# 51-039.net
KiCad netlist of a schematic drawn in Altium Designer
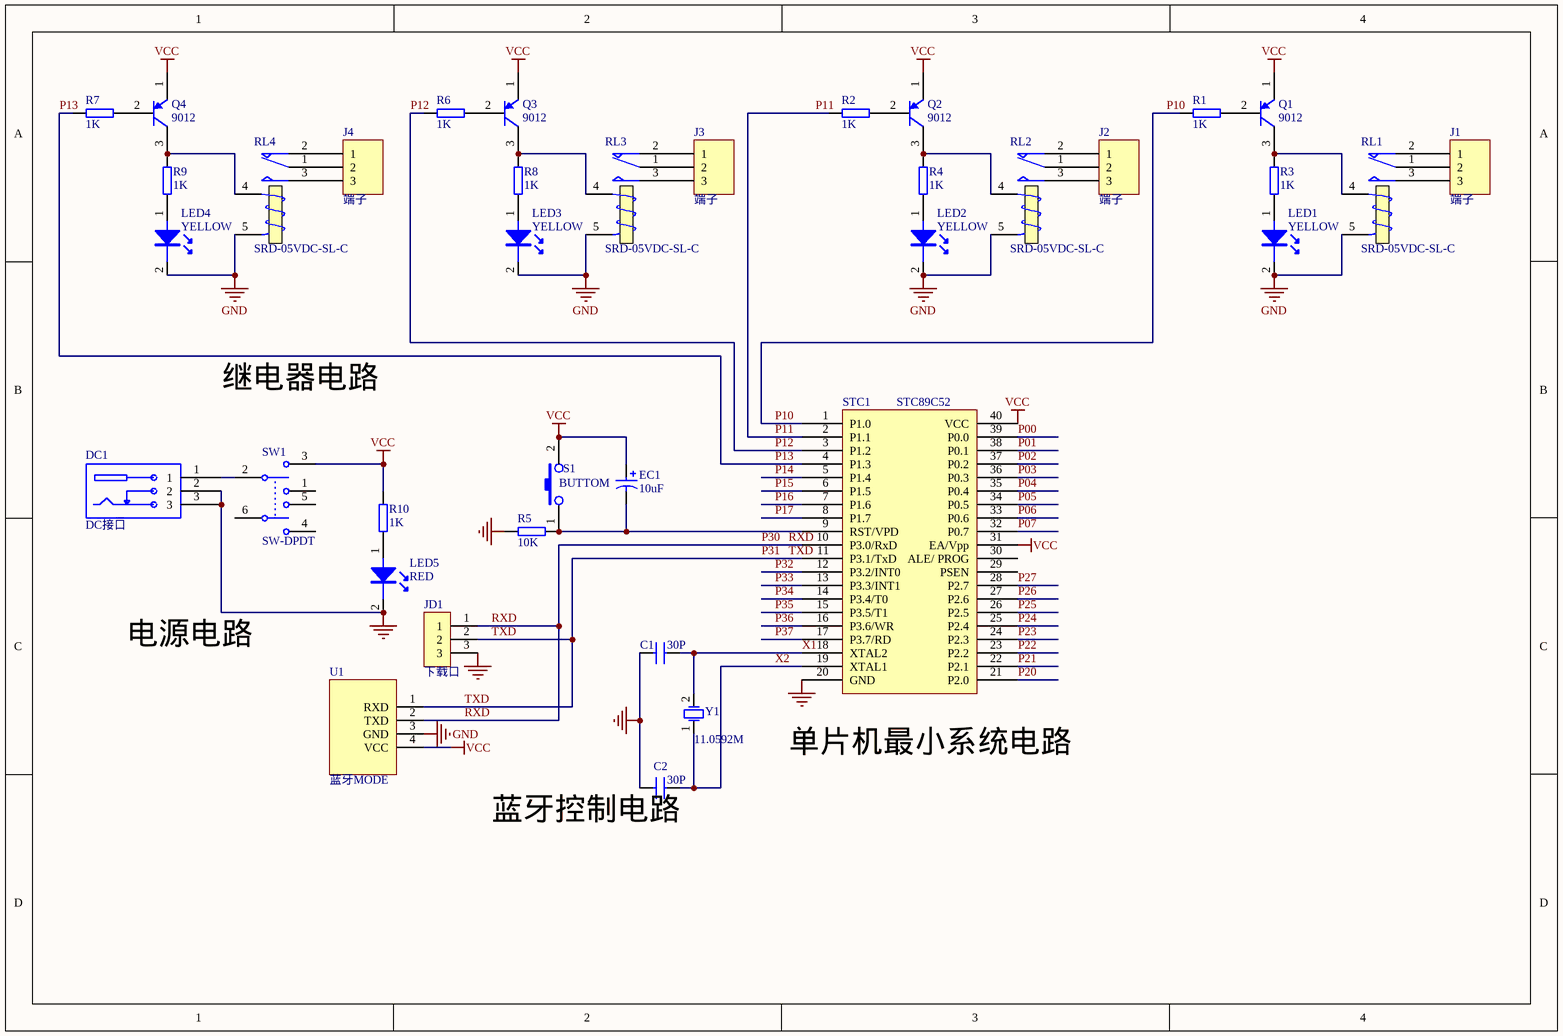
[diagram p0: 51-039原理图（源文件格式）.SCHDOC]

(export (version "E")
  (design (tool "Eeschema 10.0.6"))
  (components
    (comp (ref "C1")
      (value "30P")
      (footprint "RAD-0.1")
      (description "无极性电容")
      (libsource (lib "参考") (part "CAP"))
    )
    (comp (ref "C2")
      (value "30P")
      (footprint "RAD-0.1")
      (description "无极性电容")
      (libsource (lib "参考") (part "CAP"))
    )
    (comp (ref "DC1")
      (value "DC接口")
      (footprint "DC-JACK-002")
      (description "DC接口（分大小）")
      (libsource (lib "参考") (part "DC接口"))
    )
    (comp (ref "EC1")
      (value "10uF")
      (footprint "RB.1/.2")
      (description "极性电容")
      (libsource (lib "参考") (part "CAP_EC"))
    )
    (comp (ref "J1")
      (value "端子")
      (footprint "5.08三芯接线端子")
      (description "接线端子3芯")
      (fields (field (name "PUBLISHER") "Altium Limited"))
      (libsource (lib "参考") (part "CON3"))
    )
    (comp (ref "J2")
      (value "端子")
      (footprint "5.08三芯接线端子")
      (description "接线端子3芯")
      (fields (field (name "PUBLISHER") "Altium Limited"))
      (libsource (lib "参考") (part "CON3"))
    )
    (comp (ref "J3")
      (value "端子")
      (footprint "5.08三芯接线端子")
      (description "接线端子3芯")
      (fields (field (name "PUBLISHER") "Altium Limited"))
      (libsource (lib "参考") (part "CON3"))
    )
    (comp (ref "J4")
      (value "端子")
      (footprint "5.08三芯接线端子")
      (description "接线端子3芯")
      (fields (field (name "PUBLISHER") "Altium Limited"))
      (libsource (lib "参考") (part "CON3"))
    )
    (comp (ref "JD1")
      (value "下载口")
      (footprint "下载串口")
      (description "下载口2.54排针")
      (libsource (lib "参考") (part "下载口"))
    )
    (comp (ref "LED1")
      (value "YELLOW")
      (footprint "LED_D3MM12")
      (description "LED灯")
      (libsource (lib "参考") (part "LED"))
    )
    (comp (ref "LED2")
      (value "YELLOW")
      (footprint "LED_D3MM12")
      (description "LED灯")
      (libsource (lib "参考") (part "LED"))
    )
    (comp (ref "LED3")
      (value "YELLOW")
      (footprint "LED_D3MM12")
      (description "LED灯")
      (libsource (lib "参考") (part "LED"))
    )
    (comp (ref "LED4")
      (value "YELLOW")
      (footprint "LED_D3MM12")
      (description "LED灯")
      (libsource (lib "参考") (part "LED"))
    )
    (comp (ref "LED5")
      (value "RED")
      (footprint "LED_D3MM12")
      (description "LED灯")
      (libsource (lib "参考") (part "LED"))
    )
    (comp (ref "Q1")
      (value "9012")
      (footprint "TO-92")
      (description "直插三极管")
      (libsource (lib "参考") (part "9012"))
    )
    (comp (ref "Q2")
      (value "9012")
      (footprint "TO-92")
      (description "直插三极管")
      (libsource (lib "参考") (part "9012"))
    )
    (comp (ref "Q3")
      (value "9012")
      (footprint "TO-92")
      (description "直插三极管")
      (libsource (lib "参考") (part "9012"))
    )
    (comp (ref "Q4")
      (value "9012")
      (footprint "TO-92")
      (description "直插三极管")
      (libsource (lib "参考") (part "9012"))
    )
    (comp (ref "R1")
      (value "1K")
      (footprint "AXIAL0.3")
      (description "电阻")
      (libsource (lib "参考") (part "RES"))
    )
    (comp (ref "R2")
      (value "1K")
      (footprint "AXIAL0.3")
      (description "电阻")
      (libsource (lib "参考") (part "RES"))
    )
    (comp (ref "R3")
      (value "1K")
      (footprint "AXIAL0.3")
      (description "电阻")
      (libsource (lib "参考") (part "RES"))
    )
    (comp (ref "R4")
      (value "1K")
      (footprint "AXIAL0.3")
      (description "电阻")
      (libsource (lib "参考") (part "RES"))
    )
    (comp (ref "R5")
      (value "10K")
      (footprint "AXIAL0.3")
      (description "电阻")
      (libsource (lib "参考") (part "RES"))
    )
    (comp (ref "R6")
      (value "1K")
      (footprint "AXIAL0.3")
      (description "电阻")
      (libsource (lib "参考") (part "RES"))
    )
    (comp (ref "R7")
      (value "1K")
      (footprint "AXIAL0.3")
      (description "电阻")
      (libsource (lib "参考") (part "RES"))
    )
    (comp (ref "R8")
      (value "1K")
      (footprint "AXIAL0.3")
      (description "电阻")
      (libsource (lib "参考") (part "RES"))
    )
    (comp (ref "R9")
      (value "1K")
      (footprint "AXIAL0.3")
      (description "电阻")
      (libsource (lib "参考") (part "RES"))
    )
    (comp (ref "R10")
      (value "1K")
      (footprint "AXIAL0.3")
      (description "电阻")
      (libsource (lib "参考") (part "RES"))
    )
    (comp (ref "RL1")
      (value "SRD-05VDC-SL-C")
      (footprint "RELAY_5V51BOARD")
      (description "继电器")
      (fields (field (name "PUBLISHER") "Altium Limited"))
      (libsource (lib "参考") (part "RELAY"))
    )
    (comp (ref "RL2")
      (value "SRD-05VDC-SL-C")
      (footprint "RELAY_5V51BOARD")
      (description "继电器")
      (fields (field (name "PUBLISHER") "Altium Limited"))
      (libsource (lib "参考") (part "RELAY"))
    )
    (comp (ref "RL3")
      (value "SRD-05VDC-SL-C")
      (footprint "RELAY_5V51BOARD")
      (description "继电器")
      (fields (field (name "PUBLISHER") "Altium Limited"))
      (libsource (lib "参考") (part "RELAY"))
    )
    (comp (ref "RL4")
      (value "SRD-05VDC-SL-C")
      (footprint "RELAY_5V51BOARD")
      (description "继电器")
      (fields (field (name "PUBLISHER") "Altium Limited"))
      (libsource (lib "参考") (part "RELAY"))
    )
    (comp (ref "S1")
      (value "BUTTOM")
      (footprint "BUTTOM_6x6DIP")
      (description "按键")
      (libsource (lib "参考") (part "BUTTOM"))
    )
    (comp (ref "STC1")
      (value "STC89C52")
      (footprint "STC89")
      (description "51单片机")
      (libsource (lib "参考") (part "STC51"))
    )
    (comp (ref "SW1")
      (value "SW-DPDT")
      (footprint "SW")
      (description "电源开关")
      (fields (field (name "PUBLISHER") "Altium Limited"))
      (libsource (lib "参考") (part "SW-DPDT"))
    )
    (comp (ref "U1")
      (value "蓝牙MODE")
      (footprint "蓝牙MODE竖放")
      (description "蓝牙模块")
      (libsource (lib "参考") (part "蓝牙MODE"))
    )
    (comp (ref "Y1")
      (value "11.0592M")
      (footprint "X_HC-49")
      (description "晶振")
      (libsource (lib "参考") (part "XTAL DIP"))
    )
  )
  (nets
    (net (code "1") (name "/P00") (class "Default")
      (node (ref "STC1") (pin "39") (pinfunction "P0.0_39") (pintype "passive"))
    )
    (net (code "2") (name "/P01") (class "Default")
      (node (ref "STC1") (pin "38") (pinfunction "P0.1_38") (pintype "passive"))
    )
    (net (code "3") (name "/P02") (class "Default")
      (node (ref "STC1") (pin "37") (pinfunction "P0.2_37") (pintype "passive"))
    )
    (net (code "4") (name "/P03") (class "Default")
      (node (ref "STC1") (pin "36") (pinfunction "P0.3_36") (pintype "passive"))
    )
    (net (code "5") (name "/P04") (class "Default")
      (node (ref "STC1") (pin "35") (pinfunction "P0.4_35") (pintype "passive"))
    )
    (net (code "6") (name "/P05") (class "Default")
      (node (ref "STC1") (pin "34") (pinfunction "P0.5_34") (pintype "passive"))
    )
    (net (code "7") (name "/P06") (class "Default")
      (node (ref "STC1") (pin "33") (pinfunction "P0.6_33") (pintype "passive"))
    )
    (net (code "8") (name "/P07") (class "Default")
      (node (ref "STC1") (pin "32") (pinfunction "P0.7_32") (pintype "passive"))
    )
    (net (code "9") (name "/P10") (class "Default")
      (node (ref "R1") (pin "2") (pinfunction "2_2") (pintype "passive"))
      (node (ref "STC1") (pin "1") (pinfunction "P1.0_1") (pintype "passive"))
    )
    (net (code "10") (name "/P11") (class "Default")
      (node (ref "R2") (pin "2") (pinfunction "2_2") (pintype "passive"))
      (node (ref "STC1") (pin "2") (pinfunction "P1.1_2") (pintype "passive"))
    )
    (net (code "11") (name "/P12") (class "Default")
      (node (ref "R6") (pin "2") (pinfunction "2_2") (pintype "passive"))
      (node (ref "STC1") (pin "3") (pinfunction "P1.2_3") (pintype "passive"))
    )
    (net (code "12") (name "/P13") (class "Default")
      (node (ref "R7") (pin "2") (pinfunction "2_2") (pintype "passive"))
      (node (ref "STC1") (pin "4") (pinfunction "P1.3_4") (pintype "passive"))
    )
    (net (code "13") (name "/P14") (class "Default")
      (node (ref "STC1") (pin "5") (pinfunction "P1.4_5") (pintype "passive"))
    )
    (net (code "14") (name "/P15") (class "Default")
      (node (ref "STC1") (pin "6") (pinfunction "P1.5_6") (pintype "passive"))
    )
    (net (code "15") (name "/P16") (class "Default")
      (node (ref "STC1") (pin "7") (pinfunction "P1.6_7") (pintype "passive"))
    )
    (net (code "16") (name "/P17") (class "Default")
      (node (ref "STC1") (pin "8") (pinfunction "P1.7_8") (pintype "passive"))
    )
    (net (code "17") (name "/P20") (class "Default")
      (node (ref "STC1") (pin "21") (pinfunction "P2.0_21") (pintype "passive"))
    )
    (net (code "18") (name "/P21") (class "Default")
      (node (ref "STC1") (pin "22") (pinfunction "P2.1_22") (pintype "passive"))
    )
    (net (code "19") (name "/P22") (class "Default")
      (node (ref "STC1") (pin "23") (pinfunction "P2.2_23") (pintype "passive"))
    )
    (net (code "20") (name "/P23") (class "Default")
      (node (ref "STC1") (pin "24") (pinfunction "P2.3_24") (pintype "passive"))
    )
    (net (code "21") (name "/P24") (class "Default")
      (node (ref "STC1") (pin "25") (pinfunction "P2.4_25") (pintype "passive"))
    )
    (net (code "22") (name "/P25") (class "Default")
      (node (ref "STC1") (pin "26") (pinfunction "P2.5_26") (pintype "passive"))
    )
    (net (code "23") (name "/P26") (class "Default")
      (node (ref "STC1") (pin "27") (pinfunction "P2.6_27") (pintype "passive"))
    )
    (net (code "24") (name "/P27") (class "Default")
      (node (ref "STC1") (pin "28") (pinfunction "P2.7_28") (pintype "passive"))
    )
    (net (code "25") (name "/P30") (class "Default")
      (node (ref "JD1") (pin "1") (pinfunction "1_1") (pintype "passive"))
      (node (ref "STC1") (pin "10") (pinfunction "P3.0/RxD_10") (pintype "passive"))
      (node (ref "U1") (pin "2") (pinfunction "TXD_2") (pintype "passive"))
    )
    (net (code "26") (name "/P31") (class "Default")
      (node (ref "JD1") (pin "2") (pinfunction "2_2") (pintype "passive"))
      (node (ref "STC1") (pin "11") (pinfunction "P3.1/TxD_11") (pintype "passive"))
      (node (ref "U1") (pin "1") (pinfunction "RXD_1") (pintype "passive"))
    )
    (net (code "27") (name "/P32") (class "Default")
      (node (ref "STC1") (pin "12") (pinfunction "P3.2/INT0_12") (pintype "passive"))
    )
    (net (code "28") (name "/P33") (class "Default")
      (node (ref "STC1") (pin "13") (pinfunction "P3.3/INT1_13") (pintype "passive"))
    )
    (net (code "29") (name "/P34") (class "Default")
      (node (ref "STC1") (pin "14") (pinfunction "P3.4/T0_14") (pintype "passive"))
    )
    (net (code "30") (name "/P35") (class "Default")
      (node (ref "STC1") (pin "15") (pinfunction "P3.5/T1_15") (pintype "passive"))
    )
    (net (code "31") (name "/P36") (class "Default")
      (node (ref "STC1") (pin "16") (pinfunction "P3.6/WR_16") (pintype "passive"))
    )
    (net (code "32") (name "/P37") (class "Default")
      (node (ref "STC1") (pin "17") (pinfunction "P3.7/RD_17") (pintype "passive"))
    )
    (net (code "33") (name "/X1") (class "Default")
      (node (ref "C1") (pin "2") (pinfunction "2_2") (pintype "passive"))
      (node (ref "STC1") (pin "18") (pinfunction "XTAL2_18") (pintype "passive"))
      (node (ref "Y1") (pin "2") (pinfunction "OSC2_2") (pintype "passive"))
    )
    (net (code "34") (name "/X2") (class "Default")
      (node (ref "C2") (pin "2") (pinfunction "2_2") (pintype "passive"))
      (node (ref "STC1") (pin "19") (pinfunction "XTAL1_19") (pintype "passive"))
      (node (ref "Y1") (pin "1") (pinfunction "OSC1_1") (pintype "passive"))
    )
    (net (code "35") (name "GND") (class "Default")
      (node (ref "C1") (pin "1") (pinfunction "1_1") (pintype "passive"))
      (node (ref "C2") (pin "1") (pinfunction "1_1") (pintype "passive"))
      (node (ref "DC1") (pin "2") (pinfunction "2_2") (pintype "passive"))
      (node (ref "DC1") (pin "3") (pinfunction "3_3") (pintype "passive"))
      (node (ref "JD1") (pin "3") (pinfunction "3_3") (pintype "passive"))
      (node (ref "LED1") (pin "2") (pinfunction "2_2") (pintype "passive"))
      (node (ref "LED2") (pin "2") (pinfunction "2_2") (pintype "passive"))
      (node (ref "LED3") (pin "2") (pinfunction "2_2") (pintype "passive"))
      (node (ref "LED4") (pin "2") (pinfunction "2_2") (pintype "passive"))
      (node (ref "LED5") (pin "2") (pinfunction "2_2") (pintype "passive"))
      (node (ref "R5") (pin "1") (pinfunction "1_1") (pintype "passive"))
      (node (ref "RL1") (pin "5") (pinfunction "T2_5") (pintype "passive"))
      (node (ref "RL2") (pin "5") (pinfunction "T2_5") (pintype "passive"))
      (node (ref "RL3") (pin "5") (pinfunction "T2_5") (pintype "passive"))
      (node (ref "RL4") (pin "5") (pinfunction "T2_5") (pintype "passive"))
      (node (ref "STC1") (pin "20") (pinfunction "GND_20") (pintype "passive"))
      (node (ref "U1") (pin "3") (pinfunction "GND_3") (pintype "passive"))
    )
    (net (code "36") (name "Net-(DC1-Pad1)") (class "Default")
      (node (ref "DC1") (pin "1") (pinfunction "1_1") (pintype "passive"))
      (node (ref "SW1") (pin "2") (pinfunction "2_2") (pintype "passive"))
    )
    (net (code "37") (name "Net-(LED1-Pad1)") (class "Default")
      (node (ref "LED1") (pin "1") (pinfunction "1_1") (pintype "passive"))
      (node (ref "R3") (pin "2") (pinfunction "2_2") (pintype "passive"))
    )
    (net (code "38") (name "Net-(LED2-Pad1)") (class "Default")
      (node (ref "LED2") (pin "1") (pinfunction "1_1") (pintype "passive"))
      (node (ref "R4") (pin "2") (pinfunction "2_2") (pintype "passive"))
    )
    (net (code "39") (name "Net-(LED3-Pad1)") (class "Default")
      (node (ref "LED3") (pin "1") (pinfunction "1_1") (pintype "passive"))
      (node (ref "R8") (pin "2") (pinfunction "2_2") (pintype "passive"))
    )
    (net (code "40") (name "Net-(LED4-Pad1)") (class "Default")
      (node (ref "LED4") (pin "1") (pinfunction "1_1") (pintype "passive"))
      (node (ref "R9") (pin "2") (pinfunction "2_2") (pintype "passive"))
    )
    (net (code "41") (name "Net-(LED5-Pad1)") (class "Default")
      (node (ref "LED5") (pin "1") (pinfunction "1_1") (pintype "passive"))
      (node (ref "R10") (pin "1") (pinfunction "1_1") (pintype "passive"))
    )
    (net (code "42") (name "Net-(Q1-b)") (class "Default")
      (node (ref "Q1") (pin "2") (pinfunction "b_2") (pintype "passive"))
      (node (ref "R1") (pin "1") (pinfunction "1_1") (pintype "passive"))
    )
    (net (code "43") (name "Net-(Q1-c)") (class "Default")
      (node (ref "Q1") (pin "3") (pinfunction "c_3") (pintype "passive"))
      (node (ref "R3") (pin "1") (pinfunction "1_1") (pintype "passive"))
      (node (ref "RL1") (pin "4") (pinfunction "T1_4") (pintype "passive"))
    )
    (net (code "44") (name "Net-(Q2-b)") (class "Default")
      (node (ref "Q2") (pin "2") (pinfunction "b_2") (pintype "passive"))
      (node (ref "R2") (pin "1") (pinfunction "1_1") (pintype "passive"))
    )
    (net (code "45") (name "Net-(Q2-c)") (class "Default")
      (node (ref "Q2") (pin "3") (pinfunction "c_3") (pintype "passive"))
      (node (ref "R4") (pin "1") (pinfunction "1_1") (pintype "passive"))
      (node (ref "RL2") (pin "4") (pinfunction "T1_4") (pintype "passive"))
    )
    (net (code "46") (name "Net-(Q3-b)") (class "Default")
      (node (ref "Q3") (pin "2") (pinfunction "b_2") (pintype "passive"))
      (node (ref "R6") (pin "1") (pinfunction "1_1") (pintype "passive"))
    )
    (net (code "47") (name "Net-(Q3-c)") (class "Default")
      (node (ref "Q3") (pin "3") (pinfunction "c_3") (pintype "passive"))
      (node (ref "R8") (pin "1") (pinfunction "1_1") (pintype "passive"))
      (node (ref "RL3") (pin "4") (pinfunction "T1_4") (pintype "passive"))
    )
    (net (code "48") (name "Net-(Q4-b)") (class "Default")
      (node (ref "Q4") (pin "2") (pinfunction "b_2") (pintype "passive"))
      (node (ref "R7") (pin "1") (pinfunction "1_1") (pintype "passive"))
    )
    (net (code "49") (name "Net-(Q4-c)") (class "Default")
      (node (ref "Q4") (pin "3") (pinfunction "c_3") (pintype "passive"))
      (node (ref "R9") (pin "1") (pinfunction "1_1") (pintype "passive"))
      (node (ref "RL4") (pin "4") (pinfunction "T1_4") (pintype "passive"))
    )
    (net (code "50") (name "Net-(RL1-COM)") (class "Default")
      (node (ref "J1") (pin "2") (pinfunction "2_2") (pintype "passive"))
      (node (ref "RL1") (pin "1") (pinfunction "COM_1") (pintype "passive"))
    )
    (net (code "51") (name "Net-(RL1-NC)") (class "Default")
      (node (ref "J1") (pin "1") (pinfunction "1_1") (pintype "passive"))
      (node (ref "RL1") (pin "2") (pinfunction "NC_2") (pintype "passive"))
    )
    (net (code "52") (name "Net-(RL1-NO)") (class "Default")
      (node (ref "J1") (pin "3") (pinfunction "3_3") (pintype "passive"))
      (node (ref "RL1") (pin "3") (pinfunction "NO_3") (pintype "passive"))
    )
    (net (code "53") (name "Net-(RL2-COM)") (class "Default")
      (node (ref "J2") (pin "2") (pinfunction "2_2") (pintype "passive"))
      (node (ref "RL2") (pin "1") (pinfunction "COM_1") (pintype "passive"))
    )
    (net (code "54") (name "Net-(RL2-NC)") (class "Default")
      (node (ref "J2") (pin "1") (pinfunction "1_1") (pintype "passive"))
      (node (ref "RL2") (pin "2") (pinfunction "NC_2") (pintype "passive"))
    )
    (net (code "55") (name "Net-(RL2-NO)") (class "Default")
      (node (ref "J2") (pin "3") (pinfunction "3_3") (pintype "passive"))
      (node (ref "RL2") (pin "3") (pinfunction "NO_3") (pintype "passive"))
    )
    (net (code "56") (name "Net-(RL3-COM)") (class "Default")
      (node (ref "J3") (pin "2") (pinfunction "2_2") (pintype "passive"))
      (node (ref "RL3") (pin "1") (pinfunction "COM_1") (pintype "passive"))
    )
    (net (code "57") (name "Net-(RL3-NC)") (class "Default")
      (node (ref "J3") (pin "1") (pinfunction "1_1") (pintype "passive"))
      (node (ref "RL3") (pin "2") (pinfunction "NC_2") (pintype "passive"))
    )
    (net (code "58") (name "Net-(RL3-NO)") (class "Default")
      (node (ref "J3") (pin "3") (pinfunction "3_3") (pintype "passive"))
      (node (ref "RL3") (pin "3") (pinfunction "NO_3") (pintype "passive"))
    )
    (net (code "59") (name "Net-(RL4-COM)") (class "Default")
      (node (ref "J4") (pin "2") (pinfunction "2_2") (pintype "passive"))
      (node (ref "RL4") (pin "1") (pinfunction "COM_1") (pintype "passive"))
    )
    (net (code "60") (name "Net-(RL4-NC)") (class "Default")
      (node (ref "J4") (pin "1") (pinfunction "1_1") (pintype "passive"))
      (node (ref "RL4") (pin "2") (pinfunction "NC_2") (pintype "passive"))
    )
    (net (code "61") (name "Net-(RL4-NO)") (class "Default")
      (node (ref "J4") (pin "3") (pinfunction "3_3") (pintype "passive"))
      (node (ref "RL4") (pin "3") (pinfunction "NO_3") (pintype "passive"))
    )
    (net (code "62") (name "Net-(STC1-RST{slash}VPD)") (class "Default")
      (node (ref "EC1") (pin "2") (pinfunction "2_2") (pintype "passive"))
      (node (ref "R5") (pin "2") (pinfunction "2_2") (pintype "passive"))
      (node (ref "S1") (pin "1") (pinfunction "1_1") (pintype "passive"))
      (node (ref "STC1") (pin "9") (pinfunction "RST/VPD_9") (pintype "passive"))
    )
    (net (code "63") (name "VCC") (class "Default")
      (node (ref "EC1") (pin "1") (pinfunction "1_1") (pintype "passive"))
      (node (ref "Q1") (pin "1") (pinfunction "e_1") (pintype "passive"))
      (node (ref "Q2") (pin "1") (pinfunction "e_1") (pintype "passive"))
      (node (ref "Q3") (pin "1") (pinfunction "e_1") (pintype "passive"))
      (node (ref "Q4") (pin "1") (pinfunction "e_1") (pintype "passive"))
      (node (ref "R10") (pin "2") (pinfunction "2_2") (pintype "passive"))
      (node (ref "S1") (pin "2") (pinfunction "2_2") (pintype "passive"))
      (node (ref "STC1") (pin "31") (pinfunction "EA/Vpp_31") (pintype "passive"))
      (node (ref "STC1") (pin "40") (pinfunction "VCC_40") (pintype "passive"))
      (node (ref "SW1") (pin "3") (pinfunction "3_3") (pintype "passive"))
      (node (ref "U1") (pin "4") (pinfunction "VCC_4") (pintype "passive"))
    )
    (net (code "64") (name "unconnected-(STC1-ALE{slash}_PROG-Pad30)") (class "Default")
      (node (ref "STC1") (pin "30") (pinfunction "ALE/_PROG_30") (pintype "passive"))
    )
    (net (code "65") (name "unconnected-(STC1-PSEN-Pad29)") (class "Default")
      (node (ref "STC1") (pin "29") (pinfunction "PSEN_29") (pintype "passive"))
    )
    (net (code "66") (name "unconnected-(SW1-Pad1)") (class "Default")
      (node (ref "SW1") (pin "1") (pinfunction "1_1") (pintype "passive"))
    )
    (net (code "67") (name "unconnected-(SW1-Pad4)") (class "Default")
      (node (ref "SW1") (pin "4") (pinfunction "4_4") (pintype "passive"))
    )
    (net (code "68") (name "unconnected-(SW1-Pad5)") (class "Default")
      (node (ref "SW1") (pin "5") (pinfunction "5_5") (pintype "passive"))
    )
    (net (code "69") (name "unconnected-(SW1-Pad6)") (class "Default")
      (node (ref "SW1") (pin "6") (pinfunction "6_6") (pintype "passive"))
    )
  )
)
